# Toygether_Sch.net
KiCad netlist of a schematic drawn in Altium Designer
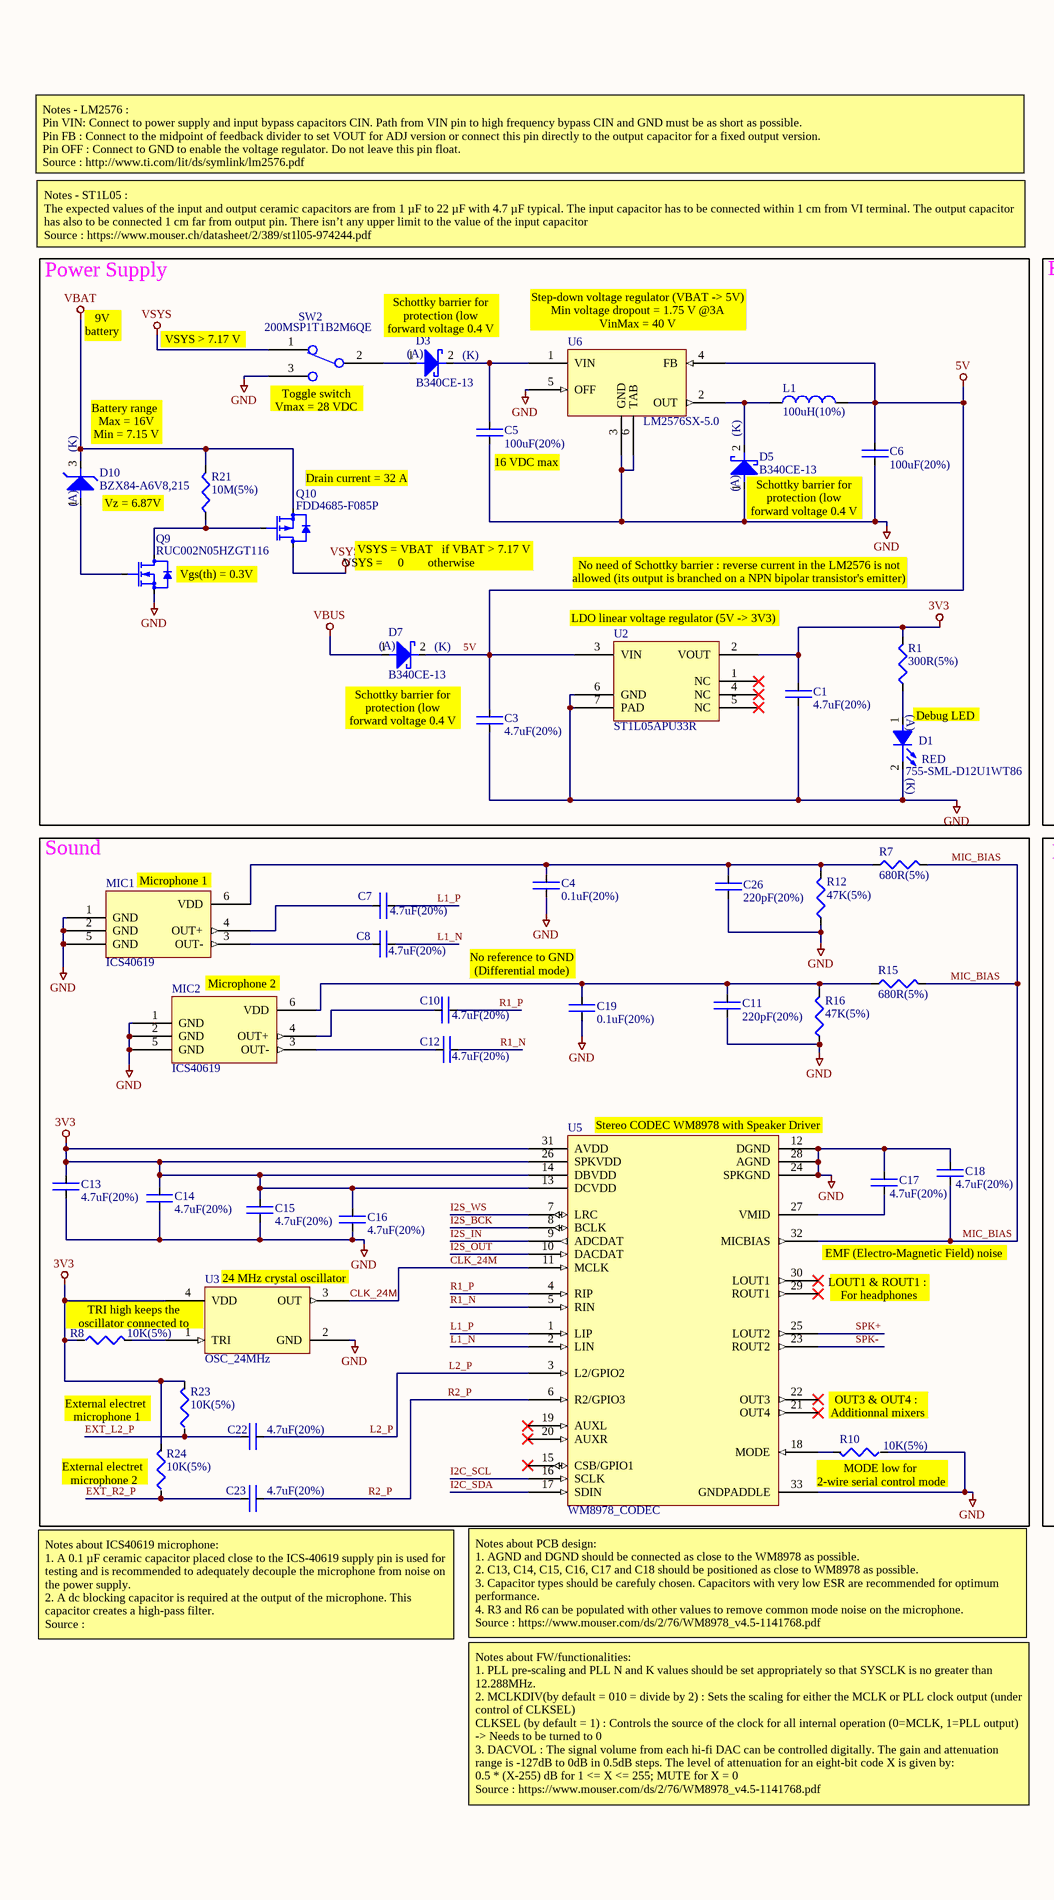
[diagram p0: Toygether_Sch.SchDoc, left]
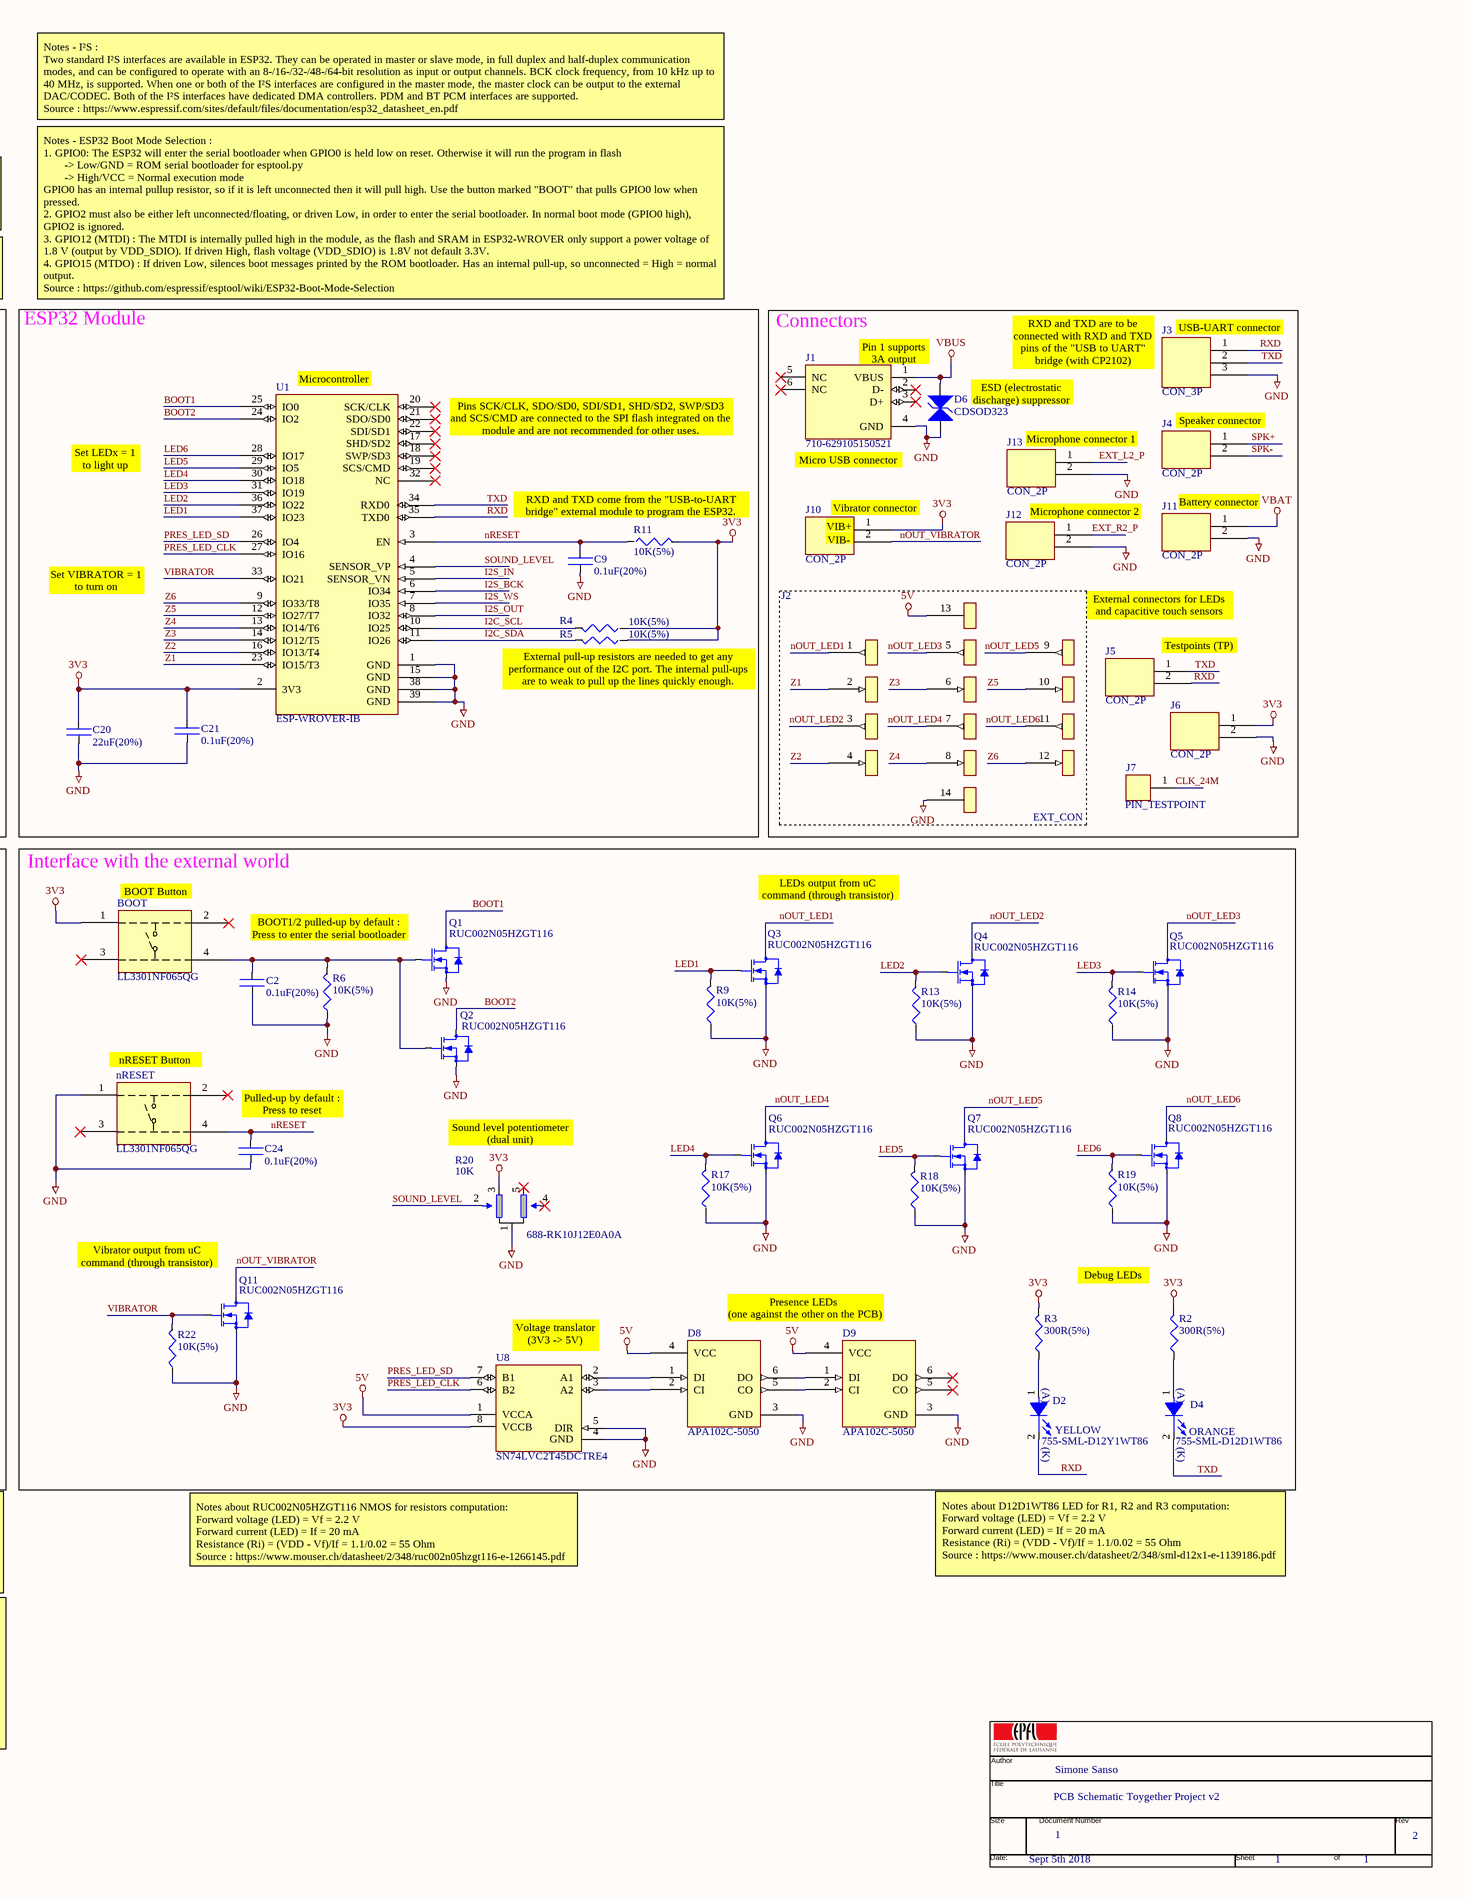
[diagram p1: Toygether_Sch.SchDoc, right]

(export (version "E")
  (design (tool "Eeschema 10.0.6"))
  (components
    (comp (ref "BOOT")
      (value "LL3301NF065QG")
      (footprint "PUSH_BUTTON-LL3301NF065QG")
      (libsource (lib "Toygether_Schlib") (part "SPST_SW"))
    )
    (comp (ref "C1")
      (value "4.7uF(20%)")
      (footprint "CAPC0603")
      (description "C1608JB1V475M080AC")
      (libsource (lib "Toygether_Schlib") (part "CAP-4.7uF(20%)"))
    )
    (comp (ref "C2")
      (value "0.1uF(20%)")
      (footprint "CAPC0603")
      (description "C1608X8R1E104M080AA")
      (libsource (lib "Toygether_Schlib") (part "CAP-0.1uF(20%)"))
    )
    (comp (ref "C3")
      (value "4.7uF(20%)")
      (footprint "CAPC0603")
      (description "C1608JB1V475M080AC")
      (libsource (lib "Toygether_Schlib") (part "CAP-4.7uF(20%)"))
    )
    (comp (ref "C4")
      (value "0.1uF(20%)")
      (footprint "CAPC0603")
      (description "C1608X8R1E104M080AA")
      (libsource (lib "Toygether_Schlib") (part "CAP-0.1uF(20%)"))
    )
    (comp (ref "C5")
      (value "100uF(20%)")
      (footprint "CAPC2312")
      (description "GRM31CR61A107ME05L")
      (libsource (lib "Toygether_Schlib") (part "CAP-100uF(20%)"))
    )
    (comp (ref "C6")
      (value "100uF(20%)")
      (footprint "CAPC2312")
      (description "GRM31CR61A107ME05L")
      (libsource (lib "Toygether_Schlib") (part "CAP-100uF(20%)"))
    )
    (comp (ref "C7")
      (value "4.7uF(20%)")
      (footprint "CAPC0603")
      (description "C1608JB1V475M080AC")
      (libsource (lib "Toygether_Schlib") (part "CAP-4.7uF(20%)"))
    )
    (comp (ref "C8")
      (value "4.7uF(20%)")
      (footprint "CAPC0603")
      (description "C1608JB1V475M080AC")
      (libsource (lib "Toygether_Schlib") (part "CAP-4.7uF(20%)"))
    )
    (comp (ref "C9")
      (value "0.1uF(20%)")
      (footprint "CAPC0603")
      (description "C1608X8R1E104M080AA")
      (libsource (lib "Toygether_Schlib") (part "CAP-0.1uF(20%)"))
    )
    (comp (ref "C10")
      (value "4.7uF(20%)")
      (footprint "CAPC0603")
      (description "C1608JB1V475M080AC")
      (libsource (lib "Toygether_Schlib") (part "CAP-4.7uF(20%)"))
    )
    (comp (ref "C11")
      (value "220pF(20%)")
      (footprint "CAPC0603")
      (description "C1608CH2A221J080AA")
      (libsource (lib "Toygether_Schlib") (part "CAP-220pF(20%)"))
    )
    (comp (ref "C12")
      (value "4.7uF(20%)")
      (footprint "CAPC0603")
      (description "C1608JB1V475M080AC")
      (libsource (lib "Toygether_Schlib") (part "CAP-4.7uF(20%)"))
    )
    (comp (ref "C13")
      (value "4.7uF(20%)")
      (footprint "CAPC0603")
      (description "C1608JB1V475M080AC")
      (libsource (lib "Toygether_Schlib") (part "CAP-4.7uF(20%)"))
    )
    (comp (ref "C14")
      (value "4.7uF(20%)")
      (footprint "CAPC0603")
      (description "C1608JB1V475M080AC")
      (libsource (lib "Toygether_Schlib") (part "CAP-4.7uF(20%)"))
    )
    (comp (ref "C15")
      (value "4.7uF(20%)")
      (footprint "CAPC0603")
      (description "C1608JB1V475M080AC")
      (libsource (lib "Toygether_Schlib") (part "CAP-4.7uF(20%)"))
    )
    (comp (ref "C16")
      (value "4.7uF(20%)")
      (footprint "CAPC0603")
      (description "C1608JB1V475M080AC")
      (libsource (lib "Toygether_Schlib") (part "CAP-4.7uF(20%)"))
    )
    (comp (ref "C17")
      (value "4.7uF(20%)")
      (footprint "CAPC0603")
      (description "C1608JB1V475M080AC")
      (libsource (lib "Toygether_Schlib") (part "CAP-4.7uF(20%)"))
    )
    (comp (ref "C18")
      (value "4.7uF(20%)")
      (footprint "CAPC0603")
      (description "C1608JB1V475M080AC")
      (libsource (lib "Toygether_Schlib") (part "CAP-4.7uF(20%)"))
    )
    (comp (ref "C19")
      (value "0.1uF(20%)")
      (footprint "CAPC0603")
      (description "C1608X8R1E104M080AA")
      (libsource (lib "Toygether_Schlib") (part "CAP-0.1uF(20%)"))
    )
    (comp (ref "C20")
      (value "22uF(20%)")
      (footprint "CAPC0603")
      (description "F380J226MMAAH1")
      (libsource (lib "Toygether_Schlib") (part "CAP-22uF(20%)"))
    )
    (comp (ref "C21")
      (value "0.1uF(20%)")
      (footprint "CAPC0603")
      (description "C1608X8R1E104M080AA")
      (libsource (lib "Toygether_Schlib") (part "CAP-0.1uF(20%)"))
    )
    (comp (ref "C22")
      (value "4.7uF(20%)")
      (footprint "CAPC0603")
      (description "C1608JB1V475M080AC")
      (libsource (lib "Toygether_Schlib") (part "CAP-4.7uF(20%)"))
    )
    (comp (ref "C23")
      (value "4.7uF(20%)")
      (footprint "CAPC0603")
      (description "C1608JB1V475M080AC")
      (libsource (lib "Toygether_Schlib") (part "CAP-4.7uF(20%)"))
    )
    (comp (ref "C24")
      (value "0.1uF(20%)")
      (footprint "CAPC0603")
      (description "C1608X8R1E104M080AA")
      (libsource (lib "Toygether_Schlib") (part "CAP-0.1uF(20%)"))
    )
    (comp (ref "C26")
      (value "220pF(20%)")
      (footprint "CAPC0603")
      (description "C1608CH2A221J080AA")
      (libsource (lib "Toygether_Schlib") (part "CAP-220pF(20%)"))
    )
    (comp (ref "D1")
      (value "SML-D12U1WT86")
      (footprint "SML-D12U1WT86")
      (description "SML-D12U1WT86-2.2V-20mA")
      (fields (field (name "SUPPLIER PART NUMBER 1") "755-SML-D12U1WT86"))
      (libsource (lib "Toygether_Schlib") (part "RED_LED"))
    )
    (comp (ref "D2")
      (value "SML-D12Y1WT86")
      (footprint "SML-D12U1WT86")
      (description "SML-D12Y1WT86_YELLOW-LED")
      (fields (field (name "SUPPLIER PART NUMBER 1") "755-SML-D12Y1WT86"))
      (libsource (lib "Toygether_Schlib") (part "YELLOW_LED"))
    )
    (comp (ref "D3")
      (value "B340CE-13")
      (footprint "SCH_DIODE-B3xxCE")
      (libsource (lib "Toygether_Schlib") (part "SCH_DIODE"))
    )
    (comp (ref "D4")
      (value "SML-D12D1W")
      (footprint "SML-D12U1WT86")
      (description "SML-D12D1WT86_ORANGE-LED")
      (fields (field (name "SUPPLIER PART NUMBER 1") "755-SML-D12D1WT86"))
      (libsource (lib "Toygether_Schlib") (part "ORANGE_LED"))
    )
    (comp (ref "D5")
      (value "B340CE-13")
      (footprint "SCH_DIODE-B3xxCE")
      (libsource (lib "Toygether_Schlib") (part "SCH_DIODE"))
    )
    (comp (ref "D6")
      (value "CDSOD323")
      (footprint "SOD-323-SCHOTTKY_DIODE-30V/0.5A")
      (description "CDSOD323-T05LC - ESD Suppressors / TVS Diodes Bidirectional Ultra Low Cap")
      (libsource (lib "Toygether_Schlib") (part "BIDIRECTIONAL_DIODE"))
    )
    (comp (ref "D7")
      (value "B340CE-13")
      (footprint "SCH_DIODE-B3xxCE")
      (libsource (lib "Toygether_Schlib") (part "SCH_DIODE"))
    )
    (comp (ref "D8")
      (value "APA102C-5050")
      (footprint "APA102C-5050")
      (libsource (lib "Toygether_Schlib") (part "APA102C"))
    )
    (comp (ref "D9")
      (value "APA102C-5050")
      (footprint "APA102C-5050")
      (libsource (lib "Toygether_Schlib") (part "APA102C"))
    )
    (comp (ref "D10")
      (value "BZX84-A6V8,215")
      (footprint "ZEN_DIODE-SOT23")
      (libsource (lib "Toygether_Schlib") (part "ZEN_DIODE-6.15V"))
    )
    (comp (ref "J1")
      (value "710-629105150521")
      (footprint "USB-MICRO-TYPE-B-FEM")
      (description "USB Micro SMT Type B Horizontal")
      (libsource (lib "Toygether_Schlib") (part "USB-MICRO-TYPE-B_CON_6P"))
    )
    (comp (ref "J2")
      (value "EXT_CON")
      (footprint "EXT_CON_14P")
      (description "External connector to the LEDs and capacitive touch sensors (on the plush toy)")
      (libsource (lib "Toygether_Schlib") (part "EXT_CON"))
    )
    (comp (ref "J3")
      (value "CON_3P")
      (footprint "CON_3P")
      (description "3 Positions Header, Breakaway Connector 0.100\" (2.54mm) Through Hole Tin")
      (libsource (lib "Toygether_Schlib") (part "CON_3P"))
    )
    (comp (ref "J4")
      (value "CON_2P")
      (footprint "CON_2P")
      (description "2 Positions Header, Breakaway Connector 0.100\" (2.54mm) Through Hole Tin")
      (libsource (lib "Toygether_Schlib") (part "CON_2P"))
    )
    (comp (ref "J5")
      (value "CON_2P")
      (footprint "CON_2P")
      (description "2 Positions Header, Breakaway Connector 0.100\" (2.54mm) Through Hole Tin")
      (libsource (lib "Toygether_Schlib") (part "CON_2P"))
    )
    (comp (ref "J6")
      (value "CON_2P")
      (footprint "CON_2P")
      (description "2 Positions Header, Breakaway Connector 0.100\" (2.54mm) Through Hole Tin")
      (libsource (lib "Toygether_Schlib") (part "CON_2P"))
    )
    (comp (ref "J7")
      (value "PIN_TESTPOINT")
      (footprint "PIN_TESTPOINT")
      (description "1 Position Header, Breakaway Connector 0.100\" (2.54mm) Through Hole Tin")
      (libsource (lib "Toygether_Schlib") (part "PIN_TESTPOINT"))
    )
    (comp (ref "J10")
      (value "CON_2P")
      (footprint "CON_2P")
      (description "2 Positions Header, Breakaway Connector 0.100\" (2.54mm) Through Hole Tin")
      (libsource (lib "Toygether_Schlib") (part "CON_2P"))
    )
    (comp (ref "J11")
      (value "CON_2P")
      (footprint "CON_2P")
      (description "2 Positions Header, Breakaway Connector 0.100\" (2.54mm) Through Hole Tin")
      (libsource (lib "Toygether_Schlib") (part "CON_2P"))
    )
    (comp (ref "J12")
      (value "CON_2P")
      (footprint "CON_2P")
      (description "2 Positions Header, Breakaway Connector 0.100\" (2.54mm) Through Hole Tin")
      (libsource (lib "Toygether_Schlib") (part "CON_2P"))
    )
    (comp (ref "J13")
      (value "CON_2P")
      (footprint "CON_2P")
      (description "2 Positions Header, Breakaway Connector 0.100\" (2.54mm) Through Hole Tin")
      (libsource (lib "Toygether_Schlib") (part "CON_2P"))
    )
    (comp (ref "L1")
      (value "100uH(10%)")
      (footprint "IND1307-100uH")
      (description "SDR1307A-101K")
      (libsource (lib "Toygether_Schlib") (part "IND-100uH(10%)"))
    )
    (comp (ref "MIC1")
      (value "ICS40619")
      (footprint "MIC-ICS40619")
      (description "Differential analog top-port microphone")
      (libsource (lib "Toygether_Schlib") (part "MIC-ICS40619"))
    )
    (comp (ref "MIC2")
      (value "ICS40619")
      (footprint "MIC-ICS40619")
      (description "Differential analog top-port microphone")
      (libsource (lib "Toygether_Schlib") (part "MIC-ICS40619"))
    )
    (comp (ref "nRESET")
      (value "LL3301NF065QG")
      (footprint "PUSH_BUTTON-LL3301NF065QG")
      (libsource (lib "Toygether_Schlib") (part "SPST_SW"))
    )
    (comp (ref "Q1")
      (value "RUC002N05HZGT116")
      (footprint "MOS-N_RUC002N05")
      (description "RUC002N05HZGT116 (N-CH/50V/2.2R/200mA)")
      (libsource (lib "Toygether_Schlib") (part "MOSFET_N-CH_RUC002N05HZGT116"))
    )
    (comp (ref "Q2")
      (value "RUC002N05HZGT116")
      (footprint "MOS-N_RUC002N05")
      (description "RUC002N05HZGT116 (N-CH/50V/2.2R/200mA)")
      (libsource (lib "Toygether_Schlib") (part "MOSFET_N-CH_RUC002N05HZGT116"))
    )
    (comp (ref "Q3")
      (value "RUC002N05HZGT116")
      (footprint "MOS-N_RUC002N05")
      (description "RUC002N05HZGT116 (N-CH/50V/2.2R/200mA)")
      (libsource (lib "Toygether_Schlib") (part "MOSFET_N-CH_RUC002N05HZGT116"))
    )
    (comp (ref "Q4")
      (value "RUC002N05HZGT116")
      (footprint "MOS-N_RUC002N05")
      (description "RUC002N05HZGT116 (N-CH/50V/2.2R/200mA)")
      (libsource (lib "Toygether_Schlib") (part "MOSFET_N-CH_RUC002N05HZGT116"))
    )
    (comp (ref "Q5")
      (value "RUC002N05HZGT116")
      (footprint "MOS-N_RUC002N05")
      (description "RUC002N05HZGT116 (N-CH/50V/2.2R/200mA)")
      (libsource (lib "Toygether_Schlib") (part "MOSFET_N-CH_RUC002N05HZGT116"))
    )
    (comp (ref "Q6")
      (value "RUC002N05HZGT116")
      (footprint "MOS-N_RUC002N05")
      (description "RUC002N05HZGT116 (N-CH/50V/2.2R/200mA)")
      (libsource (lib "Toygether_Schlib") (part "MOSFET_N-CH_RUC002N05HZGT116"))
    )
    (comp (ref "Q7")
      (value "RUC002N05HZGT116")
      (footprint "MOS-N_RUC002N05")
      (description "RUC002N05HZGT116 (N-CH/50V/2.2R/200mA)")
      (libsource (lib "Toygether_Schlib") (part "MOSFET_N-CH_RUC002N05HZGT116"))
    )
    (comp (ref "Q8")
      (value "RUC002N05HZGT116")
      (footprint "MOS-N_RUC002N05")
      (description "RUC002N05HZGT116 (N-CH/50V/2.2R/200mA)")
      (libsource (lib "Toygether_Schlib") (part "MOSFET_N-CH_RUC002N05HZGT116"))
    )
    (comp (ref "Q9")
      (value "RUC002N05HZGT116")
      (footprint "MOS-N_RUC002N05")
      (description "RUC002N05HZGT116 (N-CH/50V/2.2R/200mA)")
      (libsource (lib "Toygether_Schlib") (part "MOSFET_N-CH_RUC002N05HZGT116"))
    )
    (comp (ref "Q10")
      (value "FDD4685-F085P")
      (footprint "MOS-P_FDD4685")
      (description "FDD4685-F085P(P-CH/40V/35mR/32A)")
      (libsource (lib "Toygether_Schlib") (part "MOSFET_P-CH_FDD4685-F085P"))
    )
    (comp (ref "Q11")
      (value "RUC002N05HZGT116")
      (footprint "MOS-N_RUC002N05")
      (description "RUC002N05HZGT116 (N-CH/50V/2.2R/200mA)")
      (libsource (lib "Toygether_Schlib") (part "MOSFET_N-CH_RUC002N05HZGT116"))
    )
    (comp (ref "R1")
      (value "300R(5%)")
      (footprint "RC0603")
      (description "RC0603JR-07300RL")
      (libsource (lib "Toygether_Schlib") (part "RES-300R(5%)"))
    )
    (comp (ref "R2")
      (value "300R(5%)")
      (footprint "RC0603")
      (description "RC0603JR-07300RL")
      (libsource (lib "Toygether_Schlib") (part "RES-300R(5%)"))
    )
    (comp (ref "R3")
      (value "300R(5%)")
      (footprint "RC0603")
      (description "RC0603JR-07300RL")
      (libsource (lib "Toygether_Schlib") (part "RES-300R(5%)"))
    )
    (comp (ref "R4")
      (value "10K(5%)")
      (footprint "RC0603")
      (description "RC0603JR-0710KL")
      (libsource (lib "Toygether_Schlib") (part "RES-10K(5%)"))
    )
    (comp (ref "R5")
      (value "10K(5%)")
      (footprint "RC0603")
      (description "RC0603JR-0710KL")
      (libsource (lib "Toygether_Schlib") (part "RES-10K(5%)"))
    )
    (comp (ref "R6")
      (value "10K(5%)")
      (footprint "RC0603")
      (description "RC0603JR-0710KL")
      (libsource (lib "Toygether_Schlib") (part "RES-10K(5%)"))
    )
    (comp (ref "R7")
      (value "680R(5%)")
      (footprint "RC0603")
      (description "RC0603JR-07680RL")
      (libsource (lib "Toygether_Schlib") (part "RES-680R(5%)"))
    )
    (comp (ref "R8")
      (value "10K(5%)")
      (footprint "RC0603")
      (description "RC0603JR-0710KL")
      (libsource (lib "Toygether_Schlib") (part "RES-10K(5%)"))
    )
    (comp (ref "R9")
      (value "10K(5%)")
      (footprint "RC0603")
      (description "RC0603JR-0710KL")
      (libsource (lib "Toygether_Schlib") (part "RES-10K(5%)"))
    )
    (comp (ref "R10")
      (value "10K(5%)")
      (footprint "RC0603")
      (description "RC0603JR-0710KL")
      (libsource (lib "Toygether_Schlib") (part "RES-10K(5%)"))
    )
    (comp (ref "R11")
      (value "10K(5%)")
      (footprint "RC0603")
      (description "RC0603JR-0710KL")
      (libsource (lib "Toygether_Schlib") (part "RES-10K(5%)"))
    )
    (comp (ref "R12")
      (value "47K(5%)")
      (footprint "RC0603")
      (description "RC0603JR-0747KL")
      (libsource (lib "Toygether_Schlib") (part "RES-47K(5%)"))
    )
    (comp (ref "R13")
      (value "10K(5%)")
      (footprint "RC0603")
      (description "RC0603JR-0710KL")
      (libsource (lib "Toygether_Schlib") (part "RES-10K(5%)"))
    )
    (comp (ref "R14")
      (value "10K(5%)")
      (footprint "RC0603")
      (description "RC0603JR-0710KL")
      (libsource (lib "Toygether_Schlib") (part "RES-10K(5%)"))
    )
    (comp (ref "R15")
      (value "680R(5%)")
      (footprint "RC0603")
      (description "RC0603JR-07680RL")
      (libsource (lib "Toygether_Schlib") (part "RES-680R(5%)"))
    )
    (comp (ref "R16")
      (value "47K(5%)")
      (footprint "RC0603")
      (description "RC0603JR-0747KL")
      (libsource (lib "Toygether_Schlib") (part "RES-47K(5%)"))
    )
    (comp (ref "R17")
      (value "10K(5%)")
      (footprint "RC0603")
      (description "RC0603JR-0710KL")
      (libsource (lib "Toygether_Schlib") (part "RES-10K(5%)"))
    )
    (comp (ref "R18")
      (value "10K(5%)")
      (footprint "RC0603")
      (description "RC0603JR-0710KL")
      (libsource (lib "Toygether_Schlib") (part "RES-10K(5%)"))
    )
    (comp (ref "R19")
      (value "10K(5%)")
      (footprint "RC0603")
      (description "RC0603JR-0710KL")
      (libsource (lib "Toygether_Schlib") (part "RES-10K(5%)"))
    )
    (comp (ref "R20")
      (value "10K")
      (footprint "POT-RK10J12E0A0A")
      (description "RK10J12E0A0A")
      (fields (field (name "SUPPLIER PART NUMBER 1") "688-RK10J12E0A0A"))
      (libsource (lib "Toygether_Schlib") (part "POT-10K"))
    )
    (comp (ref "R21")
      (value "10M(5%)")
      (footprint "RC0603")
      (description "CRCW060310M0DHEAP")
      (libsource (lib "Toygether_Schlib") (part "RES-10M(5%)"))
    )
    (comp (ref "R22")
      (value "10K(5%)")
      (footprint "RC0603")
      (description "RC0603JR-0710KL")
      (libsource (lib "Toygether_Schlib") (part "RES-10K(5%)"))
    )
    (comp (ref "R23")
      (value "10K(5%)")
      (footprint "RC0603")
      (description "RC0603JR-0710KL")
      (libsource (lib "Toygether_Schlib") (part "RES-10K(5%)"))
    )
    (comp (ref "R24")
      (value "10K(5%)")
      (footprint "RC0603")
      (description "RC0603JR-0710KL")
      (libsource (lib "Toygether_Schlib") (part "RES-10K(5%)"))
    )
    (comp (ref "SW2")
      (value "200MSP1T1B2M6QE")
      (footprint "SPDT- 200MSP1T1B2M6QE")
      (libsource (lib "Toygether_Schlib") (part "SPDT_SW"))
    )
    (comp (ref "T") (value "TITLE_BLOCK") (libsource (lib "Toygether_Schlib") (part "TITLE_BLOCK")))
    (comp (ref "U1")
      (value "ESP-WROVER-IB")
      (footprint "ESP32-WROVER-I")
      (libsource (lib "Toygether_Schlib") (part "ESP-WROVER-IB"))
    )
    (comp (ref "U2")
      (value "ST1L05APU33R")
      (footprint "LDO-ST1L05")
      (description "Low drop linear voltage regulator")
      (libsource (lib "Toygether_Schlib") (part "LDO-3.3"))
    )
    (comp (ref "U3")
      (value "OSC_24MHz")
      (footprint "OSC_24MHz")
      (description "Crystal Oscillator for CODEC")
      (libsource (lib "Toygether_Schlib") (part "OSC_24MHz"))
    )
    (comp (ref "U5")
      (value "WM8978_CODEC")
      (footprint "WM8978_CODEC")
      (description "Stereo CODEC WM8978 with Speaker Driver")
      (libsource (lib "Toygether_Schlib") (part "WM8978_CODEC"))
    )
    (comp (ref "U6")
      (value "LM2576SX-5.0")
      (footprint "LM2576SX-STEP_DOWN-5.0")
      (description "LM2576SX-5.0/NOPB step down voltage regulator")
      (libsource (lib "Toygether_Schlib") (part "STEP_DOWN_LM2576SX-5.0"))
    )
    (comp (ref "U8")
      (value "SN74LVC2T45DCTRE4")
      (footprint "VOLTAGE_TRANSLATOR_3.3-5V")
      (description "Translation - Voltage Levels DUAL-BIT DUAL SUPPLY TRANSCEIVER")
      (libsource (lib "Toygether_Schlib") (part "VOLTAGE_TRANSLATOR_3.3-5V"))
    )
  )
  (nets
    (net (code "1") (name "/BOOT1") (class "Default")
      (node (ref "Q1") (pin "3") (pinfunction "3_3") (pintype "passive"))
      (node (ref "U1") (pin "25") (pinfunction "IO0_25") (pintype "bidirectional"))
    )
    (net (code "2") (name "/BOOT2") (class "Default")
      (node (ref "Q2") (pin "3") (pinfunction "3_3") (pintype "passive"))
      (node (ref "U1") (pin "24") (pinfunction "IO2_24") (pintype "bidirectional"))
    )
    (net (code "3") (name "/CLK_24M") (class "Default")
      (node (ref "J7") (pin "1") (pinfunction "Testpoint_1") (pintype "passive"))
      (node (ref "U3") (pin "3") (pinfunction "OUT_3") (pintype "output"))
      (node (ref "U5") (pin "11") (pinfunction "MCLK_11") (pintype "input"))
    )
    (net (code "4") (name "/EXT_L2_P") (class "Default")
      (node (ref "C22") (pin "1") (pinfunction "1_1") (pintype "passive"))
      (node (ref "J13") (pin "1") (pinfunction "1_1") (pintype "passive"))
      (node (ref "R23") (pin "1") (pinfunction "1_1") (pintype "passive"))
    )
    (net (code "5") (name "/EXT_R2_P") (class "Default")
      (node (ref "C23") (pin "1") (pinfunction "1_1") (pintype "passive"))
      (node (ref "J12") (pin "1") (pinfunction "1_1") (pintype "passive"))
      (node (ref "R24") (pin "1") (pinfunction "1_1") (pintype "passive"))
    )
    (net (code "6") (name "/I2C_SCL") (class "Default")
      (node (ref "R4") (pin "2") (pinfunction "2_2") (pintype "passive"))
      (node (ref "U1") (pin "10") (pinfunction "IO25_10") (pintype "bidirectional"))
      (node (ref "U5") (pin "16") (pinfunction "SCLK_16") (pintype "input"))
    )
    (net (code "7") (name "/I2C_SDA") (class "Default")
      (node (ref "R5") (pin "2") (pinfunction "2_2") (pintype "passive"))
      (node (ref "U1") (pin "11") (pinfunction "IO26_11") (pintype "bidirectional"))
      (node (ref "U5") (pin "17") (pinfunction "SDIN_17") (pintype "input"))
    )
    (net (code "8") (name "/I2S_BCK") (class "Default")
      (node (ref "U1") (pin "6") (pinfunction "IO34_6") (pintype "input"))
      (node (ref "U5") (pin "8") (pinfunction "BCLK_8") (pintype "bidirectional"))
    )
    (net (code "9") (name "/I2S_IN") (class "Default")
      (node (ref "U1") (pin "5") (pinfunction "SENSOR_VN_5") (pintype "input"))
      (node (ref "U5") (pin "9") (pinfunction "ADCDAT_9") (pintype "output"))
    )
    (net (code "10") (name "/I2S_OUT") (class "Default")
      (node (ref "U1") (pin "8") (pinfunction "IO32_8") (pintype "bidirectional"))
      (node (ref "U5") (pin "10") (pinfunction "DACDAT_10") (pintype "input"))
    )
    (net (code "11") (name "/I2S_WS") (class "Default")
      (node (ref "U1") (pin "7") (pinfunction "IO35_7") (pintype "input"))
      (node (ref "U5") (pin "7") (pinfunction "LRC_7") (pintype "bidirectional"))
    )
    (net (code "12") (name "/L1_N") (class "Default")
      (node (ref "C8") (pin "1") (pinfunction "1_1") (pintype "passive"))
      (node (ref "U5") (pin "2") (pinfunction "LIN_2") (pintype "input"))
    )
    (net (code "13") (name "/L1_P") (class "Default")
      (node (ref "C7") (pin "1") (pinfunction "1_1") (pintype "passive"))
      (node (ref "U5") (pin "1") (pinfunction "LIP_1") (pintype "input"))
    )
    (net (code "14") (name "/L2_P") (class "Default")
      (node (ref "C22") (pin "2") (pinfunction "2_2") (pintype "passive"))
      (node (ref "U5") (pin "3") (pinfunction "L2/GPIO2_3") (pintype "input"))
    )
    (net (code "15") (name "/LED1") (class "Default")
      (node (ref "Q3") (pin "1") (pinfunction "1_1") (pintype "passive"))
      (node (ref "R9") (pin "2") (pinfunction "2_2") (pintype "passive"))
      (node (ref "U1") (pin "37") (pinfunction "IO23_37") (pintype "bidirectional"))
    )
    (net (code "16") (name "/LED2") (class "Default")
      (node (ref "Q4") (pin "1") (pinfunction "1_1") (pintype "passive"))
      (node (ref "R13") (pin "2") (pinfunction "2_2") (pintype "passive"))
      (node (ref "U1") (pin "36") (pinfunction "IO22_36") (pintype "bidirectional"))
    )
    (net (code "17") (name "/LED3") (class "Default")
      (node (ref "Q5") (pin "1") (pinfunction "1_1") (pintype "passive"))
      (node (ref "R14") (pin "2") (pinfunction "2_2") (pintype "passive"))
      (node (ref "U1") (pin "31") (pinfunction "IO19_31") (pintype "bidirectional"))
    )
    (net (code "18") (name "/LED4") (class "Default")
      (node (ref "Q6") (pin "1") (pinfunction "1_1") (pintype "passive"))
      (node (ref "R17") (pin "2") (pinfunction "2_2") (pintype "passive"))
      (node (ref "U1") (pin "30") (pinfunction "IO18_30") (pintype "bidirectional"))
    )
    (net (code "19") (name "/LED5") (class "Default")
      (node (ref "Q7") (pin "1") (pinfunction "1_1") (pintype "passive"))
      (node (ref "R18") (pin "2") (pinfunction "2_2") (pintype "passive"))
      (node (ref "U1") (pin "29") (pinfunction "IO5_29") (pintype "bidirectional"))
    )
    (net (code "20") (name "/LED6") (class "Default")
      (node (ref "Q8") (pin "1") (pinfunction "1_1") (pintype "passive"))
      (node (ref "R19") (pin "2") (pinfunction "2_2") (pintype "passive"))
      (node (ref "U1") (pin "28") (pinfunction "IO17_28") (pintype "bidirectional"))
    )
    (net (code "21") (name "/MIC_BIAS") (class "Default")
      (node (ref "C18") (pin "1") (pinfunction "1_1") (pintype "passive"))
      (node (ref "R15") (pin "2") (pinfunction "2_2") (pintype "passive"))
      (node (ref "R7") (pin "2") (pinfunction "2_2") (pintype "passive"))
      (node (ref "U5") (pin "32") (pinfunction "MICBIAS_32") (pintype "output"))
    )
    (net (code "22") (name "/PRES_LED_CLK") (class "Default")
      (node (ref "U1") (pin "27") (pinfunction "IO16_27") (pintype "bidirectional"))
      (node (ref "U8") (pin "6") (pinfunction "B2_6") (pintype "bidirectional"))
    )
    (net (code "23") (name "/PRES_LED_SD") (class "Default")
      (node (ref "U1") (pin "26") (pinfunction "IO4_26") (pintype "bidirectional"))
      (node (ref "U8") (pin "7") (pinfunction "B1_7") (pintype "bidirectional"))
    )
    (net (code "24") (name "/R1_N") (class "Default")
      (node (ref "C12") (pin "1") (pinfunction "1_1") (pintype "passive"))
      (node (ref "U5") (pin "5") (pinfunction "RIN_5") (pintype "input"))
    )
    (net (code "25") (name "/R1_P") (class "Default")
      (node (ref "C10") (pin "1") (pinfunction "1_1") (pintype "passive"))
      (node (ref "U5") (pin "4") (pinfunction "RIP_4") (pintype "input"))
    )
    (net (code "26") (name "/R2_P") (class "Default")
      (node (ref "C23") (pin "2") (pinfunction "2_2") (pintype "passive"))
      (node (ref "U5") (pin "6") (pinfunction "R2/GPIO3_6") (pintype "input"))
    )
    (net (code "27") (name "/RXD") (class "Default")
      (node (ref "D2") (pin "2") (pinfunction "2_2") (pintype "passive"))
      (node (ref "J3") (pin "1") (pinfunction "1_1") (pintype "passive"))
      (node (ref "J5") (pin "2") (pinfunction "2_2") (pintype "passive"))
      (node (ref "U1") (pin "35") (pinfunction "TXD0_35") (pintype "bidirectional"))
    )
    (net (code "28") (name "/SOUND_LEVEL") (class "Default")
      (node (ref "R20") (pin "2") (pinfunction "2_2") (pintype "passive"))
      (node (ref "U1") (pin "4") (pinfunction "SENSOR_VP_4") (pintype "input"))
    )
    (net (code "29") (name "/SPK+") (class "Default")
      (node (ref "J4") (pin "1") (pinfunction "1_1") (pintype "passive"))
      (node (ref "U5") (pin "25") (pinfunction "LOUT2_25") (pintype "output"))
    )
    (net (code "30") (name "/SPK-") (class "Default")
      (node (ref "J4") (pin "2") (pinfunction "2_2") (pintype "passive"))
      (node (ref "U5") (pin "23") (pinfunction "ROUT2_23") (pintype "output"))
    )
    (net (code "31") (name "/TXD") (class "Default")
      (node (ref "D4") (pin "2") (pinfunction "2_2") (pintype "passive"))
      (node (ref "J3") (pin "2") (pinfunction "2_2") (pintype "passive"))
      (node (ref "J5") (pin "1") (pinfunction "1_1") (pintype "passive"))
      (node (ref "U1") (pin "34") (pinfunction "RXD0_34") (pintype "bidirectional"))
    )
    (net (code "32") (name "/VIBRATOR") (class "Default")
      (node (ref "Q11") (pin "1") (pinfunction "1_1") (pintype "passive"))
      (node (ref "R22") (pin "2") (pinfunction "2_2") (pintype "passive"))
      (node (ref "U1") (pin "33") (pinfunction "IO21_33") (pintype "bidirectional"))
    )
    (net (code "33") (name "/Z1") (class "Default")
      (node (ref "J2") (pin "2") (pintype "input"))
      (node (ref "U1") (pin "23") (pinfunction "IO15/T3_23") (pintype "bidirectional"))
    )
    (net (code "34") (name "/Z2") (class "Default")
      (node (ref "J2") (pin "4") (pintype "input"))
      (node (ref "U1") (pin "16") (pinfunction "IO13/T4_16") (pintype "bidirectional"))
    )
    (net (code "35") (name "/Z3") (class "Default")
      (node (ref "J2") (pin "6") (pintype "input"))
      (node (ref "U1") (pin "14") (pinfunction "IO12/T5_14") (pintype "bidirectional"))
    )
    (net (code "36") (name "/Z4") (class "Default")
      (node (ref "J2") (pin "8") (pintype "input"))
      (node (ref "U1") (pin "13") (pinfunction "IO14/T6_13") (pintype "bidirectional"))
    )
    (net (code "37") (name "/Z5") (class "Default")
      (node (ref "J2") (pin "10") (pintype "input"))
      (node (ref "U1") (pin "12") (pinfunction "IO27/T7_12") (pintype "bidirectional"))
    )
    (net (code "38") (name "/Z6") (class "Default")
      (node (ref "J2") (pin "12") (pintype "input"))
      (node (ref "U1") (pin "9") (pinfunction "IO33/T8_9") (pintype "bidirectional"))
    )
    (net (code "39") (name "/nOUT_LED1") (class "Default")
      (node (ref "J2") (pin "1") (pintype "output"))
      (node (ref "Q3") (pin "3") (pinfunction "3_3") (pintype "passive"))
    )
    (net (code "40") (name "/nOUT_LED2") (class "Default")
      (node (ref "J2") (pin "3") (pintype "output"))
      (node (ref "Q4") (pin "3") (pinfunction "3_3") (pintype "passive"))
    )
    (net (code "41") (name "/nOUT_LED3") (class "Default")
      (node (ref "J2") (pin "5") (pintype "output"))
      (node (ref "Q5") (pin "3") (pinfunction "3_3") (pintype "passive"))
    )
    (net (code "42") (name "/nOUT_LED4") (class "Default")
      (node (ref "J2") (pin "7") (pintype "output"))
      (node (ref "Q6") (pin "3") (pinfunction "3_3") (pintype "passive"))
    )
    (net (code "43") (name "/nOUT_LED5") (class "Default")
      (node (ref "J2") (pin "9") (pintype "output"))
      (node (ref "Q7") (pin "3") (pinfunction "3_3") (pintype "passive"))
    )
    (net (code "44") (name "/nOUT_LED6") (class "Default")
      (node (ref "J2") (pin "11") (pintype "output"))
      (node (ref "Q8") (pin "3") (pinfunction "3_3") (pintype "passive"))
    )
    (net (code "45") (name "/nOUT_VIBRATOR") (class "Default")
      (node (ref "J10") (pin "2") (pinfunction "2_2") (pintype "passive"))
      (node (ref "Q11") (pin "3") (pinfunction "3_3") (pintype "passive"))
    )
    (net (code "46") (name "/nRESET") (class "Default")
      (node (ref "C24") (pin "2") (pinfunction "2_2") (pintype "passive"))
      (node (ref "C9") (pin "2") (pinfunction "2_2") (pintype "passive"))
      (node (ref "R11") (pin "1") (pinfunction "1_1") (pintype "passive"))
      (node (ref "U1") (pin "3") (pinfunction "EN_3") (pintype "input"))
      (node (ref "nRESET") (pin "4") (pinfunction "4_4") (pintype "passive"))
    )
    (net (code "47") (name "3V3") (class "Default")
      (node (ref "BOOT") (pin "1") (pinfunction "1_1") (pintype "passive"))
      (node (ref "C1") (pin "2") (pinfunction "2_2") (pintype "passive"))
      (node (ref "C13") (pin "2") (pinfunction "2_2") (pintype "passive"))
      (node (ref "C14") (pin "2") (pinfunction "2_2") (pintype "passive"))
      (node (ref "C15") (pin "2") (pinfunction "2_2") (pintype "passive"))
      (node (ref "C16") (pin "2") (pinfunction "2_2") (pintype "passive"))
      (node (ref "C20") (pin "2") (pinfunction "2_2") (pintype "passive"))
      (node (ref "C21") (pin "2") (pinfunction "2_2") (pintype "passive"))
      (node (ref "J10") (pin "1") (pinfunction "1_1") (pintype "passive"))
      (node (ref "J6") (pin "1") (pinfunction "1_1") (pintype "passive"))
      (node (ref "R1") (pin "2") (pinfunction "2_2") (pintype "passive"))
      (node (ref "R11") (pin "2") (pinfunction "2_2") (pintype "passive"))
      (node (ref "R2") (pin "2") (pinfunction "2_2") (pintype "passive"))
      (node (ref "R20") (pin "3") (pinfunction "3_3") (pintype "passive"))
      (node (ref "R23") (pin "2") (pinfunction "2_2") (pintype "passive"))
      (node (ref "R24") (pin "2") (pinfunction "2_2") (pintype "passive"))
      (node (ref "R3") (pin "2") (pinfunction "2_2") (pintype "passive"))
      (node (ref "R4") (pin "1") (pinfunction "1_1") (pintype "passive"))
      (node (ref "R5") (pin "1") (pinfunction "1_1") (pintype "passive"))
      (node (ref "R8") (pin "1") (pinfunction "1_1") (pintype "passive"))
      (node (ref "U1") (pin "2") (pinfunction "3V3_2") (pintype "power_in"))
      (node (ref "U2") (pin "2") (pinfunction "VOUT_2") (pintype "power_in"))
      (node (ref "U3") (pin "4") (pinfunction "VDD_4") (pintype "power_in"))
      (node (ref "U5") (pin "13") (pinfunction "DCVDD_13") (pintype "power_in"))
      (node (ref "U5") (pin "14") (pinfunction "DBVDD_14") (pintype "power_in"))
      (node (ref "U5") (pin "26") (pinfunction "SPKVDD_26") (pintype "power_in"))
      (node (ref "U5") (pin "31") (pinfunction "AVDD_31") (pintype "power_in"))
      (node (ref "U8") (pin "8") (pinfunction "VCCB_8") (pintype "power_in"))
    )
    (net (code "48") (name "5V") (class "Default")
      (node (ref "C3") (pin "2") (pinfunction "2_2") (pintype "passive"))
      (node (ref "C6") (pin "2") (pinfunction "2_2") (pintype "passive"))
      (node (ref "D7") (pin "2") (pinfunction "K_2") (pintype "passive"))
      (node (ref "D8") (pin "4") (pinfunction "VCC_4") (pintype "power_in"))
      (node (ref "D9") (pin "4") (pinfunction "VCC_4") (pintype "power_in"))
      (node (ref "J2") (pin "13") (pintype "power_in"))
      (node (ref "L1") (pin "2") (pinfunction "2_2") (pintype "passive"))
      (node (ref "U2") (pin "3") (pinfunction "VIN_3") (pintype "power_in"))
      (node (ref "U6") (pin "4") (pinfunction "FB_4") (pintype "input"))
      (node (ref "U8") (pin "1") (pinfunction "VCCA_1") (pintype "power_in"))
    )
    (net (code "49") (name "GND") (class "Default")
      (node (ref "C1") (pin "1") (pinfunction "1_1") (pintype "passive"))
      (node (ref "C11") (pin "1") (pinfunction "1_1") (pintype "passive"))
      (node (ref "C13") (pin "1") (pinfunction "1_1") (pintype "passive"))
      (node (ref "C14") (pin "1") (pinfunction "1_1") (pintype "passive"))
      (node (ref "C15") (pin "1") (pinfunction "1_1") (pintype "passive"))
      (node (ref "C16") (pin "1") (pinfunction "1_1") (pintype "passive"))
      (node (ref "C17") (pin "2") (pinfunction "2_2") (pintype "passive"))
      (node (ref "C18") (pin "2") (pinfunction "2_2") (pintype "passive"))
      (node (ref "C19") (pin "1") (pinfunction "1_1") (pintype "passive"))
      (node (ref "C2") (pin "1") (pinfunction "1_1") (pintype "passive"))
      (node (ref "C20") (pin "1") (pinfunction "1_1") (pintype "passive"))
      (node (ref "C21") (pin "1") (pinfunction "1_1") (pintype "passive"))
      (node (ref "C24") (pin "1") (pinfunction "1_1") (pintype "passive"))
      (node (ref "C26") (pin "1") (pinfunction "1_1") (pintype "passive"))
      (node (ref "C3") (pin "1") (pinfunction "1_1") (pintype "passive"))
      (node (ref "C4") (pin "1") (pinfunction "1_1") (pintype "passive"))
      (node (ref "C5") (pin "1") (pinfunction "1_1") (pintype "passive"))
      (node (ref "C6") (pin "1") (pinfunction "1_1") (pintype "passive"))
      (node (ref "C9") (pin "1") (pinfunction "1_1") (pintype "passive"))
      (node (ref "D1") (pin "2") (pinfunction "2_2") (pintype "passive"))
      (node (ref "D5") (pin "1") (pinfunction "A_1") (pintype "passive"))
      (node (ref "D6") (pin "1") (pinfunction "C_1") (pintype "passive"))
      (node (ref "D8") (pin "3") (pinfunction "GND_3") (pintype "power_in"))
      (node (ref "D9") (pin "3") (pinfunction "GND_3") (pintype "power_in"))
      (node (ref "J1") (pin "4") (pinfunction "GND_4") (pintype "power_in"))
      (node (ref "J11") (pin "2") (pinfunction "2_2") (pintype "passive"))
      (node (ref "J12") (pin "2") (pinfunction "2_2") (pintype "passive"))
      (node (ref "J13") (pin "2") (pinfunction "2_2") (pintype "passive"))
      (node (ref "J2") (pin "14") (pintype "power_in"))
      (node (ref "J3") (pin "3") (pinfunction "3_3") (pintype "passive"))
      (node (ref "J6") (pin "2") (pinfunction "2_2") (pintype "passive"))
      (node (ref "MIC1") (pin "1") (pinfunction "GND_1") (pintype "power_in"))
      (node (ref "MIC1") (pin "2") (pinfunction "GND_2") (pintype "power_in"))
      (node (ref "MIC1") (pin "5") (pinfunction "GND_5") (pintype "power_in"))
      (node (ref "MIC2") (pin "1") (pinfunction "GND_1") (pintype "power_in"))
      (node (ref "MIC2") (pin "2") (pinfunction "GND_2") (pintype "power_in"))
      (node (ref "MIC2") (pin "5") (pinfunction "GND_5") (pintype "power_in"))
      (node (ref "Q1") (pin "2") (pinfunction "2_2") (pintype "passive"))
      (node (ref "Q11") (pin "2") (pinfunction "2_2") (pintype "passive"))
      (node (ref "Q2") (pin "2") (pinfunction "2_2") (pintype "passive"))
      (node (ref "Q3") (pin "2") (pinfunction "2_2") (pintype "passive"))
      (node (ref "Q4") (pin "2") (pinfunction "2_2") (pintype "passive"))
      (node (ref "Q5") (pin "2") (pinfunction "2_2") (pintype "passive"))
      (node (ref "Q6") (pin "2") (pinfunction "2_2") (pintype "passive"))
      (node (ref "Q7") (pin "2") (pinfunction "2_2") (pintype "passive"))
      (node (ref "Q8") (pin "2") (pinfunction "2_2") (pintype "passive"))
      (node (ref "Q9") (pin "2") (pinfunction "2_2") (pintype "passive"))
      (node (ref "R10") (pin "1") (pinfunction "1_1") (pintype "passive"))
      (node (ref "R12") (pin "1") (pinfunction "1_1") (pintype "passive"))
      (node (ref "R13") (pin "1") (pinfunction "1_1") (pintype "passive"))
      (node (ref "R14") (pin "1") (pinfunction "1_1") (pintype "passive"))
      (node (ref "R16") (pin "1") (pinfunction "1_1") (pintype "passive"))
      (node (ref "R17") (pin "1") (pinfunction "1_1") (pintype "passive"))
      (node (ref "R18") (pin "1") (pinfunction "1_1") (pintype "passive"))
      (node (ref "R19") (pin "1") (pinfunction "1_1") (pintype "passive"))
      (node (ref "R20") (pin "1") (pinfunction "1_1") (pintype "passive"))
      (node (ref "R22") (pin "1") (pinfunction "1_1") (pintype "passive"))
      (node (ref "R6") (pin "1") (pinfunction "1_1") (pintype "passive"))
      (node (ref "R9") (pin "1") (pinfunction "1_1") (pintype "passive"))
      (node (ref "SW2") (pin "3") (pinfunction "3_3") (pintype "passive"))
      (node (ref "U1") (pin "1") (pinfunction "GND_1") (pintype "power_in"))
      (node (ref "U1") (pin "15") (pinfunction "GND_15") (pintype "power_in"))
      (node (ref "U1") (pin "38") (pinfunction "GND_38") (pintype "power_in"))
      (node (ref "U1") (pin "39") (pinfunction "GND_39") (pintype "power_in"))
      (node (ref "U2") (pin "6") (pinfunction "GND_6") (pintype "power_in"))
      (node (ref "U2") (pin "7") (pinfunction "PAD_7") (pintype "power_in"))
      (node (ref "U3") (pin "2") (pinfunction "GND_2") (pintype "power_in"))
      (node (ref "U5") (pin "12") (pinfunction "DGND_12") (pintype "power_in"))
      (node (ref "U5") (pin "24") (pinfunction "SPKGND_24") (pintype "power_in"))
      (node (ref "U5") (pin "28") (pinfunction "AGND_28") (pintype "power_in"))
      (node (ref "U5") (pin "33") (pinfunction "GNDPADDLE_33") (pintype "power_in"))
      (node (ref "U6") (pin "3") (pinfunction "GND_3") (pintype "power_in"))
      (node (ref "U6") (pin "5") (pinfunction "OFF_5") (pintype "input"))
      (node (ref "U6") (pin "6") (pinfunction "TAB_6") (pintype "power_in"))
      (node (ref "U8") (pin "4") (pinfunction "GND_4") (pintype "power_in"))
      (node (ref "U8") (pin "5") (pinfunction "DIR_5") (pintype "input"))
      (node (ref "nRESET") (pin "1") (pinfunction "1_1") (pintype "passive"))
    )
    (net (code "50") (name "Net-(BOOT-Pad4)") (class "Default")
      (node (ref "BOOT") (pin "4") (pinfunction "4_4") (pintype "passive"))
      (node (ref "C2") (pin "2") (pinfunction "2_2") (pintype "passive"))
      (node (ref "Q1") (pin "1") (pinfunction "1_1") (pintype "passive"))
      (node (ref "Q2") (pin "1") (pinfunction "1_1") (pintype "passive"))
      (node (ref "R6") (pin "2") (pinfunction "2_2") (pintype "passive"))
    )
    (net (code "51") (name "Net-(D1-Pad1)") (class "Default")
      (node (ref "D1") (pin "1") (pinfunction "1_1") (pintype "passive"))
      (node (ref "R1") (pin "1") (pinfunction "1_1") (pintype "passive"))
    )
    (net (code "52") (name "Net-(D2-Pad1)") (class "Default")
      (node (ref "D2") (pin "1") (pinfunction "1_1") (pintype "passive"))
      (node (ref "R3") (pin "1") (pinfunction "1_1") (pintype "passive"))
    )
    (net (code "53") (name "Net-(D3-A)") (class "Default")
      (node (ref "D3") (pin "1") (pinfunction "A_1") (pintype "passive"))
      (node (ref "SW2") (pin "2") (pinfunction "2_2") (pintype "passive"))
    )
    (net (code "54") (name "Net-(D3-K)") (class "Default")
      (node (ref "C5") (pin "2") (pinfunction "2_2") (pintype "passive"))
      (node (ref "D3") (pin "2") (pinfunction "K_2") (pintype "passive"))
      (node (ref "U6") (pin "1") (pinfunction "VIN_1") (pintype "power_in"))
    )
    (net (code "55") (name "Net-(D4-Pad1)") (class "Default")
      (node (ref "D4") (pin "1") (pinfunction "1_1") (pintype "passive"))
      (node (ref "R2") (pin "1") (pinfunction "1_1") (pintype "passive"))
    )
    (net (code "56") (name "Net-(D5-K)") (class "Default")
      (node (ref "D5") (pin "2") (pinfunction "K_2") (pintype "passive"))
      (node (ref "L1") (pin "1") (pinfunction "1_1") (pintype "passive"))
      (node (ref "U6") (pin "2") (pinfunction "OUT_2") (pintype "output"))
    )
    (net (code "57") (name "Net-(D8-CI)") (class "Default")
      (node (ref "D8") (pin "2") (pinfunction "CI_2") (pintype "input"))
      (node (ref "U8") (pin "3") (pinfunction "A2_3") (pintype "bidirectional"))
    )
    (net (code "58") (name "Net-(D8-CO)") (class "Default")
      (node (ref "D8") (pin "5") (pinfunction "CO_5") (pintype "output"))
      (node (ref "D9") (pin "2") (pinfunction "CI_2") (pintype "input"))
    )
    (net (code "59") (name "Net-(D8-DI)") (class "Default")
      (node (ref "D8") (pin "1") (pinfunction "DI_1") (pintype "input"))
      (node (ref "U8") (pin "2") (pinfunction "A1_2") (pintype "bidirectional"))
    )
    (net (code "60") (name "Net-(D8-DO)") (class "Default")
      (node (ref "D8") (pin "6") (pinfunction "DO_6") (pintype "output"))
      (node (ref "D9") (pin "1") (pinfunction "DI_1") (pintype "input"))
    )
    (net (code "61") (name "Net-(D10-A)") (class "Default")
      (node (ref "D10") (pin "1") (pinfunction "A_1") (pintype "passive"))
      (node (ref "Q9") (pin "1") (pinfunction "1_1") (pintype "passive"))
    )
    (net (code "62") (name "Net-(MIC1-OUT+)") (class "Default")
      (node (ref "C7") (pin "2") (pinfunction "2_2") (pintype "passive"))
      (node (ref "MIC1") (pin "4") (pinfunction "OUT+_4") (pintype "output"))
    )
    (net (code "63") (name "Net-(MIC1-OUT-)") (class "Default")
      (node (ref "C8") (pin "2") (pinfunction "2_2") (pintype "passive"))
      (node (ref "MIC1") (pin "3") (pinfunction "OUT-_3") (pintype "output"))
    )
    (net (code "64") (name "Net-(MIC1-VDD)") (class "Default")
      (node (ref "C26") (pin "2") (pinfunction "2_2") (pintype "passive"))
      (node (ref "C4") (pin "2") (pinfunction "2_2") (pintype "passive"))
      (node (ref "MIC1") (pin "6") (pinfunction "VDD_6") (pintype "passive"))
      (node (ref "R12") (pin "2") (pinfunction "2_2") (pintype "passive"))
      (node (ref "R7") (pin "1") (pinfunction "1_1") (pintype "passive"))
    )
    (net (code "65") (name "Net-(MIC2-OUT+)") (class "Default")
      (node (ref "C10") (pin "2") (pinfunction "2_2") (pintype "passive"))
      (node (ref "MIC2") (pin "4") (pinfunction "OUT+_4") (pintype "output"))
    )
    (net (code "66") (name "Net-(MIC2-OUT-)") (class "Default")
      (node (ref "C12") (pin "2") (pinfunction "2_2") (pintype "passive"))
      (node (ref "MIC2") (pin "3") (pinfunction "OUT-_3") (pintype "output"))
    )
    (net (code "67") (name "Net-(MIC2-VDD)") (class "Default")
      (node (ref "C11") (pin "2") (pinfunction "2_2") (pintype "passive"))
      (node (ref "C19") (pin "2") (pinfunction "2_2") (pintype "passive"))
      (node (ref "MIC2") (pin "6") (pinfunction "VDD_6") (pintype "passive"))
      (node (ref "R15") (pin "1") (pinfunction "1_1") (pintype "passive"))
      (node (ref "R16") (pin "2") (pinfunction "2_2") (pintype "passive"))
    )
    (net (code "68") (name "Net-(Q10-Pad1)") (class "Default")
      (node (ref "Q10") (pin "1") (pinfunction "1_1") (pintype "passive"))
      (node (ref "Q9") (pin "3") (pinfunction "3_3") (pintype "passive"))
      (node (ref "R21") (pin "1") (pinfunction "1_1") (pintype "passive"))
    )
    (net (code "69") (name "Net-(U3-TRI)") (class "Default")
      (node (ref "R8") (pin "2") (pinfunction "2_2") (pintype "passive"))
      (node (ref "U3") (pin "1") (pinfunction "TRI_1") (pintype "input"))
    )
    (net (code "70") (name "Net-(U5-MODE)") (class "Default")
      (node (ref "R10") (pin "2") (pinfunction "2_2") (pintype "passive"))
      (node (ref "U5") (pin "18") (pinfunction "MODE_18") (pintype "input"))
    )
    (net (code "71") (name "Net-(U5-VMID)") (class "Default")
      (node (ref "C17") (pin "1") (pinfunction "1_1") (pintype "passive"))
      (node (ref "U5") (pin "27") (pinfunction "VMID_27") (pintype "passive"))
    )
    (net (code "72") (name "VBAT") (class "Default")
      (node (ref "D10") (pin "3") (pinfunction "K_3") (pintype "passive"))
      (node (ref "J11") (pin "1") (pinfunction "1_1") (pintype "passive"))
      (node (ref "Q10") (pin "2") (pinfunction "2_2") (pintype "passive"))
      (node (ref "R21") (pin "2") (pinfunction "2_2") (pintype "passive"))
    )
    (net (code "73") (name "VBUS") (class "Default")
      (node (ref "D6") (pin "2") (pinfunction "C_2") (pintype "passive"))
      (node (ref "D7") (pin "1") (pinfunction "A_1") (pintype "passive"))
      (node (ref "J1") (pin "1") (pinfunction "VBUS_1") (pintype "power_in"))
    )
    (net (code "74") (name "VSYS") (class "Default")
      (node (ref "Q10") (pin "3") (pinfunction "3_3") (pintype "passive"))
      (node (ref "SW2") (pin "1") (pinfunction "1_1") (pintype "passive"))
    )
    (net (code "75") (name "unconnected-(BOOT-Pad2)") (class "Default")
      (node (ref "BOOT") (pin "2") (pinfunction "2_2") (pintype "passive+no_connect"))
    )
    (net (code "76") (name "unconnected-(BOOT-Pad3)") (class "Default")
      (node (ref "BOOT") (pin "3") (pinfunction "3_3") (pintype "passive+no_connect"))
    )
    (net (code "77") (name "unconnected-(D9-CO-Pad5)") (class "Default")
      (node (ref "D9") (pin "5") (pinfunction "CO_5") (pintype "output+no_connect"))
    )
    (net (code "78") (name "unconnected-(D9-DO-Pad6)") (class "Default")
      (node (ref "D9") (pin "6") (pinfunction "DO_6") (pintype "output+no_connect"))
    )
    (net (code "79") (name "unconnected-(J1-D+-Pad3)") (class "Default")
      (node (ref "J1") (pin "3") (pinfunction "D+_3") (pintype "bidirectional+no_connect"))
    )
    (net (code "80") (name "unconnected-(J1-D--Pad2)") (class "Default")
      (node (ref "J1") (pin "2") (pinfunction "D-_2") (pintype "bidirectional+no_connect"))
    )
    (net (code "81") (name "unconnected-(J1-NC-Pad5)") (class "Default")
      (node (ref "J1") (pin "5") (pinfunction "NC_5") (pintype "passive+no_connect"))
    )
    (net (code "82") (name "unconnected-(J1-NC-Pad6)") (class "Default")
      (node (ref "J1") (pin "6") (pinfunction "NC_6") (pintype "passive+no_connect"))
    )
    (net (code "83") (name "unconnected-(R20-Pad4)") (class "Default")
      (node (ref "R20") (pin "4") (pinfunction "4_4") (pintype "passive+no_connect"))
    )
    (net (code "84") (name "unconnected-(R20-Pad5)") (class "Default")
      (node (ref "R20") (pin "5") (pinfunction "5_5") (pintype "passive+no_connect"))
    )
    (net (code "85") (name "unconnected-(U1-NC-Pad32)") (class "Default")
      (node (ref "U1") (pin "32") (pinfunction "NC_32") (pintype "passive+no_connect"))
    )
    (net (code "86") (name "unconnected-(U1-SCK{slash}CLK-Pad20)") (class "Default")
      (node (ref "U1") (pin "20") (pinfunction "SCK/CLK_20") (pintype "bidirectional+no_connect"))
    )
    (net (code "87") (name "unconnected-(U1-SCS{slash}CMD-Pad19)") (class "Default")
      (node (ref "U1") (pin "19") (pinfunction "SCS/CMD_19") (pintype "bidirectional+no_connect"))
    )
    (net (code "88") (name "unconnected-(U1-SDI{slash}SD1-Pad22)") (class "Default")
      (node (ref "U1") (pin "22") (pinfunction "SDI/SD1_22") (pintype "bidirectional+no_connect"))
    )
    (net (code "89") (name "unconnected-(U1-SDO{slash}SD0-Pad21)") (class "Default")
      (node (ref "U1") (pin "21") (pinfunction "SDO/SD0_21") (pintype "bidirectional+no_connect"))
    )
    (net (code "90") (name "unconnected-(U1-SHD{slash}SD2-Pad17)") (class "Default")
      (node (ref "U1") (pin "17") (pinfunction "SHD/SD2_17") (pintype "bidirectional+no_connect"))
    )
    (net (code "91") (name "unconnected-(U1-SWP{slash}SD3-Pad18)") (class "Default")
      (node (ref "U1") (pin "18") (pinfunction "SWP/SD3_18") (pintype "bidirectional+no_connect"))
    )
    (net (code "92") (name "unconnected-(U2-NC-Pad1)") (class "Default")
      (node (ref "U2") (pin "1") (pinfunction "NC_1") (pintype "passive+no_connect"))
    )
    (net (code "93") (name "unconnected-(U2-NC-Pad4)") (class "Default")
      (node (ref "U2") (pin "4") (pinfunction "NC_4") (pintype "passive+no_connect"))
    )
    (net (code "94") (name "unconnected-(U2-NC-Pad5)") (class "Default")
      (node (ref "U2") (pin "5") (pinfunction "NC_5") (pintype "passive+no_connect"))
    )
    (net (code "95") (name "unconnected-(U5-AUXL-Pad19)") (class "Default")
      (node (ref "U5") (pin "19") (pinfunction "AUXL_19") (pintype "input+no_connect"))
    )
    (net (code "96") (name "unconnected-(U5-AUXR-Pad20)") (class "Default")
      (node (ref "U5") (pin "20") (pinfunction "AUXR_20") (pintype "input+no_connect"))
    )
    (net (code "97") (name "unconnected-(U5-CSB{slash}GPIO1-Pad15)") (class "Default")
      (node (ref "U5") (pin "15") (pinfunction "CSB/GPIO1_15") (pintype "bidirectional+no_connect"))
    )
    (net (code "98") (name "unconnected-(U5-LOUT1-Pad30)") (class "Default")
      (node (ref "U5") (pin "30") (pinfunction "LOUT1_30") (pintype "output+no_connect"))
    )
    (net (code "99") (name "unconnected-(U5-OUT3-Pad22)") (class "Default")
      (node (ref "U5") (pin "22") (pinfunction "OUT3_22") (pintype "output+no_connect"))
    )
    (net (code "100") (name "unconnected-(U5-OUT4-Pad21)") (class "Default")
      (node (ref "U5") (pin "21") (pinfunction "OUT4_21") (pintype "output+no_connect"))
    )
    (net (code "101") (name "unconnected-(U5-ROUT1-Pad29)") (class "Default")
      (node (ref "U5") (pin "29") (pinfunction "ROUT1_29") (pintype "output+no_connect"))
    )
    (net (code "102") (name "unconnected-(nRESET-Pad2)") (class "Default")
      (node (ref "nRESET") (pin "2") (pinfunction "2_2") (pintype "passive+no_connect"))
    )
    (net (code "103") (name "unconnected-(nRESET-Pad3)") (class "Default")
      (node (ref "nRESET") (pin "3") (pinfunction "3_3") (pintype "passive+no_connect"))
    )
  )
)
